# communication.net
KiCad netlist of a schematic drawn in Altium Designer
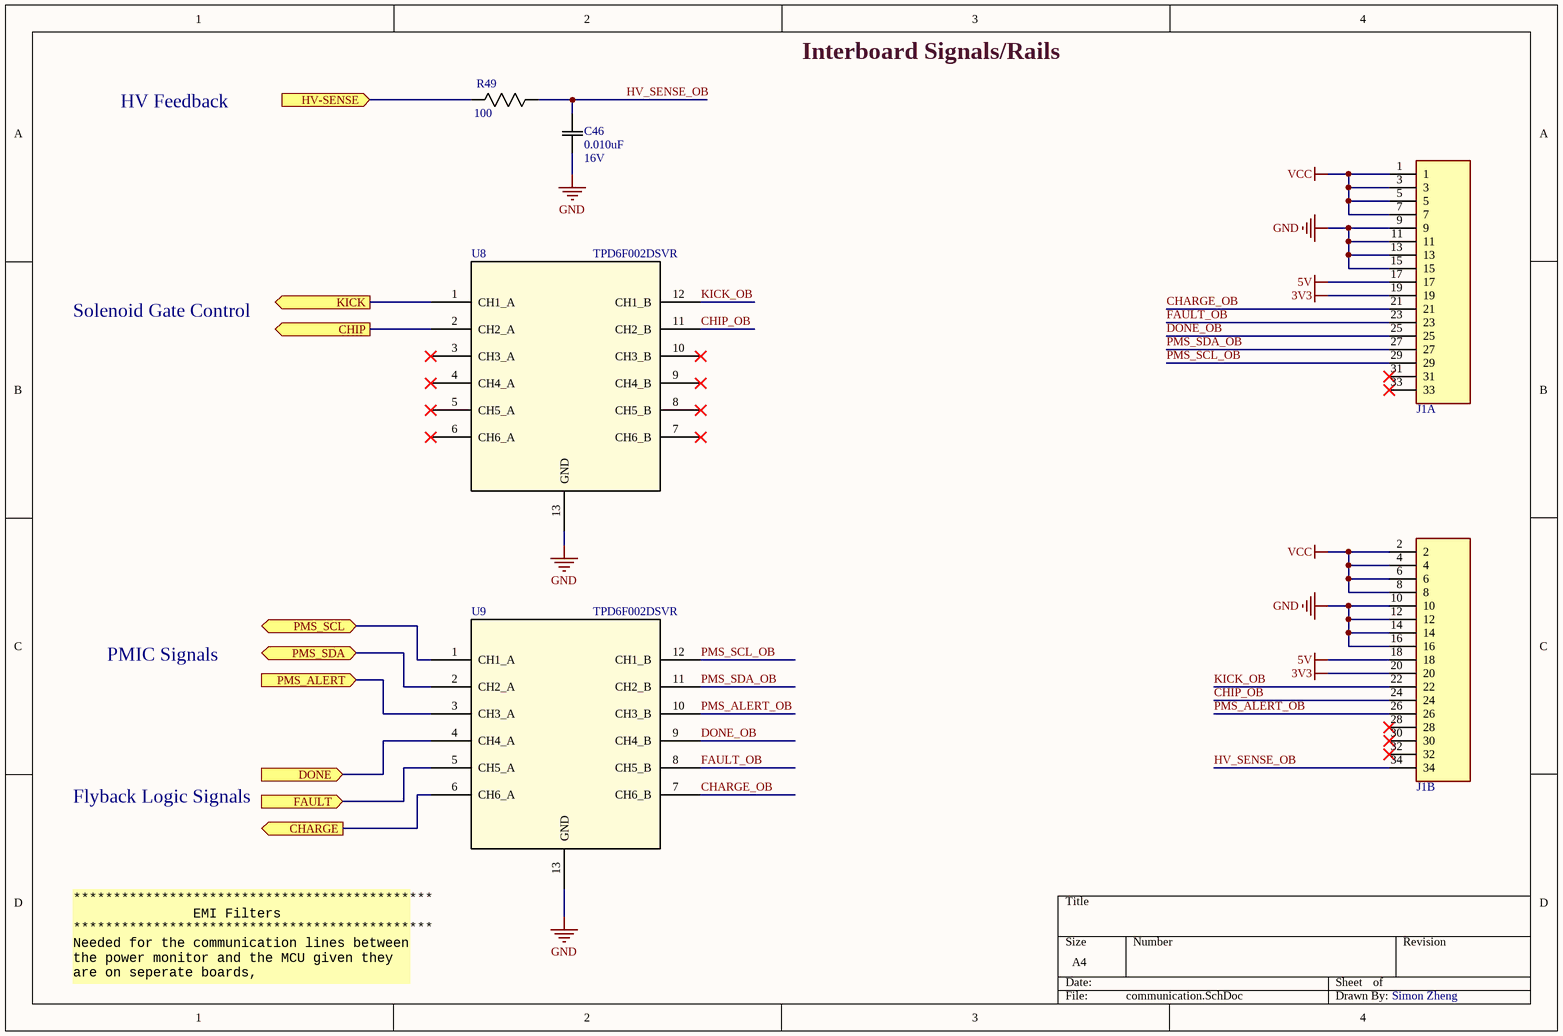
[diagram p0: communication.SchDoc]

(export (version "E")
  (design (tool "Eeschema 10.0.6"))
  (components
    (comp (ref "C46")
      (value "0.010uF")
      (footprint "0805")
      (description "CAP CER 0.010UF 16V X5R 0603/0805")
      (fields (field (name "TOLERANCE") "10%") (field (name "RATING") "16V"))
      (libsource (lib "AltiumLibraries") (part "CAP 0.010uF 16V"))
    )
    (comp (ref "J1")
      (value "0.1\" Header Female 34")
      (footprint "SAMTEC_ESQ-117-12-L-D")
      (description "Female Header THRU 34POS 2ROW 0.1\" (2.54mm) pitch")
      (libsource (lib "AltiumLibraries") (part "CN HDR 34POS 2x17"))
    )
    (comp (ref "R49")
      (value "100")
      (footprint "0805")
      (description "RES SMD 100 OHM 5% 1/8W 0805")
      (fields (field (name "TOLERANCE") "5%"))
      (libsource (lib "AltiumLibraries") (part "RES 100.0 1/8W"))
    )
    (comp (ref "U8")
      (value "TPD6F002DSVR")
      (footprint "PSON50P140X80_HS-13N")
      (description "6-Channel EMI Filter for Display Interface")
      (fields
        (field (name "MANUFACTURER") "Texas Instruments")
        (field (name "GENERIC_PART_NUMBER") "TPD6F002")
        (field (name "COPYRIGHT") "Copyright (C) 2018 Accelerated Designs. All rights reserved")
      )
      (libsource (lib "AltiumLibraries") (part "EMI FILTER TPD6F002DSVR"))
    )
    (comp (ref "U9")
      (value "TPD6F002DSVR")
      (footprint "PSON50P140X80_HS-13N")
      (description "6-Channel EMI Filter for Display Interface")
      (fields
        (field (name "MANUFACTURER") "Texas Instruments")
        (field (name "GENERIC_PART_NUMBER") "TPD6F002")
        (field (name "COPYRIGHT") "Copyright (C) 2018 Accelerated Designs. All rights reserved")
      )
      (libsource (lib "AltiumLibraries") (part "EMI FILTER TPD6F002DSVR"))
    )
  )
  (nets
    (net (code "1") (name "/CHARGE") (class "Default")
      (node (ref "U9") (pin "6") (pinfunction "CH6_A_6") (pintype "passive"))
    )
    (net (code "2") (name "/CHARGE_OB") (class "Default")
      (node (ref "J1") (pin "21") (pinfunction "21_21") (pintype "passive"))
      (node (ref "U9") (pin "7") (pinfunction "CH6_B_7") (pintype "passive"))
    )
    (net (code "3") (name "/CHIP") (class "Default")
      (node (ref "U8") (pin "2") (pinfunction "CH2_A_2") (pintype "passive"))
    )
    (net (code "4") (name "/CHIP_OB") (class "Default")
      (node (ref "J1") (pin "24") (pinfunction "24_24") (pintype "passive"))
      (node (ref "U8") (pin "11") (pinfunction "CH2_B_11") (pintype "passive"))
    )
    (net (code "5") (name "/DONE") (class "Default")
      (node (ref "U9") (pin "4") (pinfunction "CH4_A_4") (pintype "passive"))
    )
    (net (code "6") (name "/DONE_OB") (class "Default")
      (node (ref "J1") (pin "25") (pinfunction "25_25") (pintype "passive"))
      (node (ref "U9") (pin "9") (pinfunction "CH4_B_9") (pintype "passive"))
    )
    (net (code "7") (name "/FAULT") (class "Default")
      (node (ref "U9") (pin "5") (pinfunction "CH5_A_5") (pintype "passive"))
    )
    (net (code "8") (name "/FAULT_OB") (class "Default")
      (node (ref "J1") (pin "23") (pinfunction "23_23") (pintype "passive"))
      (node (ref "U9") (pin "8") (pinfunction "CH5_B_8") (pintype "passive"))
    )
    (net (code "9") (name "/HV-SENSE") (class "Default")
      (node (ref "R49") (pin "2") (pinfunction "R2_2") (pintype "passive"))
    )
    (net (code "10") (name "/HV_SENSE_OB") (class "Default")
      (node (ref "C46") (pin "1") (pinfunction "C1_1") (pintype "passive"))
      (node (ref "J1") (pin "34") (pinfunction "34_34") (pintype "passive"))
      (node (ref "R49") (pin "1") (pinfunction "R1_1") (pintype "passive"))
    )
    (net (code "11") (name "/KICK") (class "Default")
      (node (ref "U8") (pin "1") (pinfunction "CH1_A_1") (pintype "passive"))
    )
    (net (code "12") (name "/KICK_OB") (class "Default")
      (node (ref "J1") (pin "22") (pinfunction "22_22") (pintype "passive"))
      (node (ref "U8") (pin "12") (pinfunction "CH1_B_12") (pintype "passive"))
    )
    (net (code "13") (name "/PMS_ALERT") (class "Default")
      (node (ref "U9") (pin "3") (pinfunction "CH3_A_3") (pintype "passive"))
    )
    (net (code "14") (name "/PMS_ALERT_OB") (class "Default")
      (node (ref "J1") (pin "26") (pinfunction "26_26") (pintype "passive"))
      (node (ref "U9") (pin "10") (pinfunction "CH3_B_10") (pintype "passive"))
    )
    (net (code "15") (name "/PMS_SCL") (class "Default")
      (node (ref "U9") (pin "1") (pinfunction "CH1_A_1") (pintype "passive"))
    )
    (net (code "16") (name "/PMS_SCL_OB") (class "Default")
      (node (ref "J1") (pin "29") (pinfunction "29_29") (pintype "passive"))
      (node (ref "U9") (pin "12") (pinfunction "CH1_B_12") (pintype "passive"))
    )
    (net (code "17") (name "/PMS_SDA") (class "Default")
      (node (ref "U9") (pin "2") (pinfunction "CH2_A_2") (pintype "passive"))
    )
    (net (code "18") (name "/PMS_SDA_OB") (class "Default")
      (node (ref "J1") (pin "27") (pinfunction "27_27") (pintype "passive"))
      (node (ref "U9") (pin "11") (pinfunction "CH2_B_11") (pintype "passive"))
    )
    (net (code "19") (name "3V3") (class "Default")
      (node (ref "J1") (pin "19") (pinfunction "19_19") (pintype "passive"))
      (node (ref "J1") (pin "20") (pinfunction "20_20") (pintype "passive"))
    )
    (net (code "20") (name "5V") (class "Default")
      (node (ref "J1") (pin "17") (pinfunction "17_17") (pintype "passive"))
      (node (ref "J1") (pin "18") (pinfunction "18_18") (pintype "passive"))
    )
    (net (code "21") (name "GND") (class "Default")
      (node (ref "C46") (pin "2") (pinfunction "C2_2") (pintype "passive"))
      (node (ref "J1") (pin "10") (pinfunction "10_10") (pintype "passive"))
      (node (ref "J1") (pin "11") (pinfunction "11_11") (pintype "passive"))
      (node (ref "J1") (pin "12") (pinfunction "12_12") (pintype "passive"))
      (node (ref "J1") (pin "13") (pinfunction "13_13") (pintype "passive"))
      (node (ref "J1") (pin "14") (pinfunction "14_14") (pintype "passive"))
      (node (ref "J1") (pin "15") (pinfunction "15_15") (pintype "passive"))
      (node (ref "J1") (pin "16") (pinfunction "16_16") (pintype "passive"))
      (node (ref "J1") (pin "9") (pinfunction "9_9") (pintype "passive"))
      (node (ref "U8") (pin "13") (pinfunction "GND_13") (pintype "passive"))
      (node (ref "U9") (pin "13") (pinfunction "GND_13") (pintype "passive"))
    )
    (net (code "22") (name "VCC") (class "Default")
      (node (ref "J1") (pin "1") (pinfunction "1_1") (pintype "passive"))
      (node (ref "J1") (pin "2") (pinfunction "2_2") (pintype "passive"))
      (node (ref "J1") (pin "3") (pinfunction "3_3") (pintype "passive"))
      (node (ref "J1") (pin "4") (pinfunction "4_4") (pintype "passive"))
      (node (ref "J1") (pin "5") (pinfunction "5_5") (pintype "passive"))
      (node (ref "J1") (pin "6") (pinfunction "6_6") (pintype "passive"))
      (node (ref "J1") (pin "7") (pinfunction "7_7") (pintype "passive"))
      (node (ref "J1") (pin "8") (pinfunction "8_8") (pintype "passive"))
    )
    (net (code "23") (name "unconnected-(J1-Pad28)") (class "Default")
      (node (ref "J1") (pin "28") (pinfunction "28_28") (pintype "passive+no_connect"))
    )
    (net (code "24") (name "unconnected-(J1-Pad30)") (class "Default")
      (node (ref "J1") (pin "30") (pinfunction "30_30") (pintype "passive+no_connect"))
    )
    (net (code "25") (name "unconnected-(J1-Pad31)") (class "Default")
      (node (ref "J1") (pin "31") (pinfunction "31_31") (pintype "passive+no_connect"))
    )
    (net (code "26") (name "unconnected-(J1-Pad32)") (class "Default")
      (node (ref "J1") (pin "32") (pinfunction "32_32") (pintype "passive+no_connect"))
    )
    (net (code "27") (name "unconnected-(J1-Pad33)") (class "Default")
      (node (ref "J1") (pin "33") (pinfunction "33_33") (pintype "passive+no_connect"))
    )
    (net (code "28") (name "unconnected-(U8-CH3_A-Pad3)") (class "Default")
      (node (ref "U8") (pin "3") (pinfunction "CH3_A_3") (pintype "passive+no_connect"))
    )
    (net (code "29") (name "unconnected-(U8-CH3_B-Pad10)") (class "Default")
      (node (ref "U8") (pin "10") (pinfunction "CH3_B_10") (pintype "passive+no_connect"))
    )
    (net (code "30") (name "unconnected-(U8-CH4_A-Pad4)") (class "Default")
      (node (ref "U8") (pin "4") (pinfunction "CH4_A_4") (pintype "passive+no_connect"))
    )
    (net (code "31") (name "unconnected-(U8-CH4_B-Pad9)") (class "Default")
      (node (ref "U8") (pin "9") (pinfunction "CH4_B_9") (pintype "passive+no_connect"))
    )
    (net (code "32") (name "unconnected-(U8-CH5_A-Pad5)") (class "Default")
      (node (ref "U8") (pin "5") (pinfunction "CH5_A_5") (pintype "passive+no_connect"))
    )
    (net (code "33") (name "unconnected-(U8-CH5_B-Pad8)") (class "Default")
      (node (ref "U8") (pin "8") (pinfunction "CH5_B_8") (pintype "passive+no_connect"))
    )
    (net (code "34") (name "unconnected-(U8-CH6_A-Pad6)") (class "Default")
      (node (ref "U8") (pin "6") (pinfunction "CH6_A_6") (pintype "passive+no_connect"))
    )
    (net (code "35") (name "unconnected-(U8-CH6_B-Pad7)") (class "Default")
      (node (ref "U8") (pin "7") (pinfunction "CH6_B_7") (pintype "passive+no_connect"))
    )
  )
)
